# Sheet1.net
KiCad netlist of a schematic drawn in Altium Designer
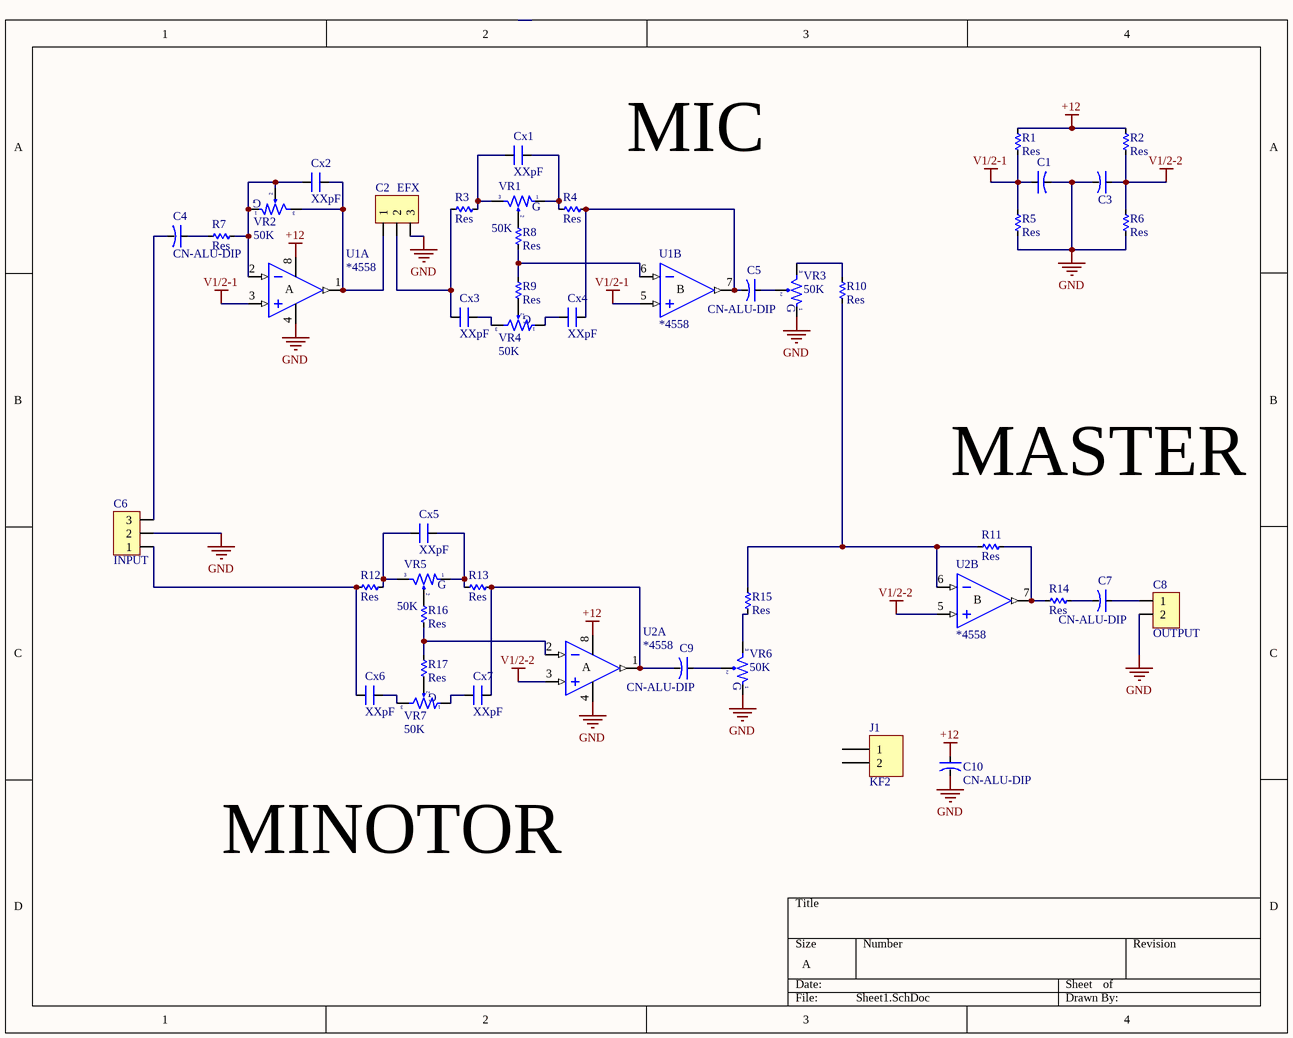
[diagram p0: Sheet1.SchDoc]

(export (version "E")
  (design (tool "Eeschema 10.0.6"))
  (components
    (comp (ref "C1")
      (value "CN-ALU-DIP")
      (footprint "CA-ALU-5")
      (description "Capacitor (Semiconductor SIM Model)")
      (fields (field (name "PUBLISHER") "Altium Limited"))
      (libsource (lib "LIBRARY") (part "CN-ALU-DIP"))
    )
    (comp (ref "C2")
      (value "EFX")
      (footprint "Header3")
      (description "Header IDC, 3 x 1 Pin Vertical 2.54mm Pitch (Non-Boxed, Male)")
      (fields
        (field (name "MANUFACTURER") "Würth Elektronik eiSos GmbH")
        (field (name "PARTNO") "613002143121")
        (field (name "CREATED BY") "Karrer Zheng")
      )
      (libsource (lib "LIBRARY") (part "Header3"))
    )
    (comp (ref "C3")
      (value "CN-ALU-DIP")
      (footprint "CA-ALU-5")
      (description "Capacitor (Semiconductor SIM Model)")
      (fields (field (name "PUBLISHER") "Altium Limited"))
      (libsource (lib "LIBRARY") (part "CN-ALU-DIP"))
    )
    (comp (ref "C4")
      (value "CN-ALU-DIP")
      (footprint "CA-ALU-5")
      (description "Capacitor (Semiconductor SIM Model)")
      (fields (field (name "PUBLISHER") "Altium Limited"))
      (libsource (lib "LIBRARY") (part "CN-ALU-DIP"))
    )
    (comp (ref "C5")
      (value "CN-ALU-DIP")
      (footprint "CA-ALU-5")
      (description "Capacitor (Semiconductor SIM Model)")
      (fields (field (name "PUBLISHER") "Altium Limited"))
      (libsource (lib "LIBRARY") (part "CN-ALU-DIP"))
    )
    (comp (ref "C6")
      (value "INPUT")
      (footprint "Header3")
      (description "Header IDC, 3 x 1 Pin Vertical 2.54mm Pitch (Non-Boxed, Male)")
      (fields
        (field (name "MANUFACTURER") "Würth Elektronik eiSos GmbH")
        (field (name "PARTNO") "613002143121")
        (field (name "CREATED BY") "Karrer Zheng")
      )
      (libsource (lib "") (part "Header3_1"))
    )
    (comp (ref "C7")
      (value "CN-ALU-DIP")
      (footprint "CA-ALU-5")
      (description "Capacitor (Semiconductor SIM Model)")
      (fields (field (name "PUBLISHER") "Altium Limited"))
      (libsource (lib "LIBRARY") (part "CN-ALU-DIP"))
    )
    (comp (ref "C8")
      (value "OUTPUT")
      (footprint "Header2")
      (description "Header IDC, 2 x 1 Pin Vertical 2.54mm Pitch (Non-Boxed, Male)")
      (fields
        (field (name "MANUFACTURER") "Würth Elektronik eiSos GmbH")
        (field (name "PARTNO") "613002143121")
        (field (name "CREATED BY") "Karrer Zheng")
      )
      (libsource (lib "LIBRARY") (part "Header2"))
    )
    (comp (ref "C9")
      (value "CN-ALU-DIP")
      (footprint "CA-ALU-5")
      (description "Capacitor (Semiconductor SIM Model)")
      (fields (field (name "PUBLISHER") "Altium Limited"))
      (libsource (lib "LIBRARY") (part "CN-ALU-DIP"))
    )
    (comp (ref "C10")
      (value "CN-ALU-DIP")
      (footprint "CA-ALU-6.3R")
      (description "Capacitor (Semiconductor SIM Model)")
      (fields (field (name "PUBLISHER") "Altium Limited"))
      (libsource (lib "") (part "CN-ALU-DIP_1"))
    )
    (comp (ref "Cx1") (value "XXpF") (footprint "CN2-O") (libsource (lib "LIBRARY") (part "CN")))
    (comp (ref "Cx2") (value "XXpF") (footprint "CN1.5") (libsource (lib "LIBRARY") (part "CN")))
    (comp (ref "Cx3") (value "XXpF") (footprint "CN2-O") (libsource (lib "LIBRARY") (part "CN")))
    (comp (ref "Cx4") (value "XXpF") (footprint "CN1.5") (libsource (lib "LIBRARY") (part "CN")))
    (comp (ref "Cx5") (value "XXpF") (footprint "CN2-O") (libsource (lib "LIBRARY") (part "CN")))
    (comp (ref "Cx6") (value "XXpF") (footprint "CN1.5") (libsource (lib "LIBRARY") (part "CN")))
    (comp (ref "Cx7") (value "XXpF") (footprint "CN1.5") (libsource (lib "LIBRARY") (part "CN")))
    (comp (ref "J1")
      (value "KF2")
      (footprint "KF2-5.08")
      (fields
        (field (name "MANUFACTURER") "Würth Elektronik eiSos GmbH")
        (field (name "PARTNO") "691103110002")
        (field (name "CREATED BY") "Karrer Zheng")
      )
      (libsource (lib "LIBRARY") (part "KF2"))
    )
    (comp (ref "R1")
      (value "Res")
      (footprint "RES-1/4W-SMALL")
      (fields
        (field (name "MANUFACTURER") "Generic Components")
        (field (name "PUBLISHER") "Altium Hobart Technology Centre")
      )
      (libsource (lib "LIBRARY") (part "Res"))
    )
    (comp (ref "R2")
      (value "Res")
      (footprint "RES-1/4W-SMALL")
      (fields
        (field (name "MANUFACTURER") "Generic Components")
        (field (name "PUBLISHER") "Altium Hobart Technology Centre")
      )
      (libsource (lib "LIBRARY") (part "Res"))
    )
    (comp (ref "R3")
      (value "Res")
      (footprint "RES-1/4W-SMALL")
      (fields
        (field (name "MANUFACTURER") "Generic Components")
        (field (name "PUBLISHER") "Altium Hobart Technology Centre")
      )
      (libsource (lib "LIBRARY") (part "Res"))
    )
    (comp (ref "R4")
      (value "Res")
      (footprint "RES-1/4W-SMALL")
      (fields
        (field (name "MANUFACTURER") "Generic Components")
        (field (name "PUBLISHER") "Altium Hobart Technology Centre")
      )
      (libsource (lib "LIBRARY") (part "Res"))
    )
    (comp (ref "R5")
      (value "Res")
      (footprint "RES-1/4W-SMALL")
      (fields
        (field (name "MANUFACTURER") "Generic Components")
        (field (name "PUBLISHER") "Altium Hobart Technology Centre")
      )
      (libsource (lib "LIBRARY") (part "Res"))
    )
    (comp (ref "R6")
      (value "Res")
      (footprint "RES-1/4W-SMALL")
      (fields
        (field (name "MANUFACTURER") "Generic Components")
        (field (name "PUBLISHER") "Altium Hobart Technology Centre")
      )
      (libsource (lib "LIBRARY") (part "Res"))
    )
    (comp (ref "R7")
      (value "Res")
      (footprint "RES-1/4W-SMALL")
      (fields
        (field (name "MANUFACTURER") "Generic Components")
        (field (name "PUBLISHER") "Altium Hobart Technology Centre")
      )
      (libsource (lib "LIBRARY") (part "Res"))
    )
    (comp (ref "R8")
      (value "Res")
      (footprint "RES-1/4W-SMALL")
      (fields
        (field (name "MANUFACTURER") "Generic Components")
        (field (name "PUBLISHER") "Altium Hobart Technology Centre")
      )
      (libsource (lib "LIBRARY") (part "Res"))
    )
    (comp (ref "R9")
      (value "Res")
      (footprint "RES-1/4W-SMALL")
      (fields
        (field (name "MANUFACTURER") "Generic Components")
        (field (name "PUBLISHER") "Altium Hobart Technology Centre")
      )
      (libsource (lib "LIBRARY") (part "Res"))
    )
    (comp (ref "R10")
      (value "Res")
      (footprint "RES-1/4W-SMALL")
      (fields
        (field (name "MANUFACTURER") "Generic Components")
        (field (name "PUBLISHER") "Altium Hobart Technology Centre")
      )
      (libsource (lib "LIBRARY") (part "Res"))
    )
    (comp (ref "R11")
      (value "Res")
      (footprint "RES-1/4W-SMALL")
      (fields
        (field (name "MANUFACTURER") "Generic Components")
        (field (name "PUBLISHER") "Altium Hobart Technology Centre")
      )
      (libsource (lib "LIBRARY") (part "Res"))
    )
    (comp (ref "R12")
      (value "Res")
      (footprint "RES-1/4W-SMALL")
      (fields
        (field (name "MANUFACTURER") "Generic Components")
        (field (name "PUBLISHER") "Altium Hobart Technology Centre")
      )
      (libsource (lib "LIBRARY") (part "Res"))
    )
    (comp (ref "R13")
      (value "Res")
      (footprint "RES-1/4W-SMALL")
      (fields
        (field (name "MANUFACTURER") "Generic Components")
        (field (name "PUBLISHER") "Altium Hobart Technology Centre")
      )
      (libsource (lib "LIBRARY") (part "Res"))
    )
    (comp (ref "R14")
      (value "Res")
      (footprint "RES-1/4W-SMALL")
      (fields
        (field (name "MANUFACTURER") "Generic Components")
        (field (name "PUBLISHER") "Altium Hobart Technology Centre")
      )
      (libsource (lib "LIBRARY") (part "Res"))
    )
    (comp (ref "R15")
      (value "Res")
      (footprint "RES-1/4W-SMALL")
      (fields
        (field (name "MANUFACTURER") "Generic Components")
        (field (name "PUBLISHER") "Altium Hobart Technology Centre")
      )
      (libsource (lib "LIBRARY") (part "Res"))
    )
    (comp (ref "R16")
      (value "Res")
      (footprint "RES-1/4W-SMALL")
      (fields
        (field (name "MANUFACTURER") "Generic Components")
        (field (name "PUBLISHER") "Altium Hobart Technology Centre")
      )
      (libsource (lib "LIBRARY") (part "Res"))
    )
    (comp (ref "R17")
      (value "Res")
      (footprint "RES-1/4W-SMALL")
      (fields
        (field (name "MANUFACTURER") "Generic Components")
        (field (name "PUBLISHER") "Altium Hobart Technology Centre")
      )
      (libsource (lib "LIBRARY") (part "Res"))
    )
    (comp (ref "U1") (value "*4558") (footprint "DIP8") (libsource (lib "LIBRARY") (part "4558")))
    (comp (ref "U2") (value "*4558") (footprint "DIP8") (libsource (lib "LIBRARY") (part "4558")))
    (comp (ref "VR1")
      (value "50K")
      (footprint "VR-S1")
      (description "Var Resistor")
      (libsource (lib "LIBRARY") (part "VR-S"))
    )
    (comp (ref "VR2")
      (value "50K")
      (footprint "VR-S2")
      (description "Var Resistor")
      (libsource (lib "LIBRARY") (part "VR-S"))
    )
    (comp (ref "VR3")
      (value "50K")
      (footprint "VR-S1")
      (description "Var Resistor")
      (libsource (lib "LIBRARY") (part "VR-S"))
    )
    (comp (ref "VR4")
      (value "50K")
      (footprint "VR-S1")
      (description "Var Resistor")
      (libsource (lib "LIBRARY") (part "VR-S"))
    )
    (comp (ref "VR5")
      (value "50K")
      (footprint "VR-S1")
      (description "Var Resistor")
      (libsource (lib "LIBRARY") (part "VR-S"))
    )
    (comp (ref "VR6")
      (value "50K")
      (footprint "VR-S1")
      (description "Var Resistor")
      (libsource (lib "LIBRARY") (part "VR-S"))
    )
    (comp (ref "VR7")
      (value "50K")
      (footprint "VR-S1")
      (description "Var Resistor")
      (libsource (lib "LIBRARY") (part "VR-S"))
    )
  )
  (nets
    (net (code "1") (name "+12") (class "Default")
      (node (ref "C10") (pin "1") (pinfunction "1_1") (pintype "passive"))
      (node (ref "R1") (pin "1") (pinfunction "1_1") (pintype "passive"))
      (node (ref "R2") (pin "1") (pinfunction "1_1") (pintype "passive"))
      (node (ref "U1") (pin "8") (pinfunction "V+_8") (pintype "power_in"))
      (node (ref "U2") (pin "8") (pinfunction "V+_8") (pintype "power_in"))
    )
    (net (code "2") (name "GND") (class "Default")
      (node (ref "C1") (pin "2") (pinfunction "2_2") (pintype "passive"))
      (node (ref "C10") (pin "2") (pinfunction "2_2") (pintype "passive"))
      (node (ref "C2") (pin "3") (pinfunction "3_3") (pintype "passive"))
      (node (ref "C3") (pin "2") (pinfunction "2_2") (pintype "passive"))
      (node (ref "C6") (pin "2") (pinfunction "2_2") (pintype "passive"))
      (node (ref "C8") (pin "2") (pinfunction "2_2") (pintype "passive"))
      (node (ref "R5") (pin "2") (pinfunction "2_2") (pintype "passive"))
      (node (ref "R6") (pin "2") (pinfunction "2_2") (pintype "passive"))
      (node (ref "U1") (pin "4") (pinfunction "V-_4") (pintype "power_in"))
      (node (ref "U2") (pin "4") (pinfunction "V-_4") (pintype "power_in"))
      (node (ref "VR3") (pin "1") (pinfunction "1_1") (pintype "passive"))
      (node (ref "VR6") (pin "1") (pinfunction "1_1") (pintype "passive"))
    )
    (net (code "3") (name "Net-(C2-Pad2)") (class "Default")
      (node (ref "C2") (pin "2") (pinfunction "2_2") (pintype "passive"))
      (node (ref "Cx3") (pin "1") (pinfunction "1_1") (pintype "passive"))
      (node (ref "R3") (pin "2") (pinfunction "2_2") (pintype "passive"))
    )
    (net (code "4") (name "Net-(C4-Pad1)") (class "Default")
      (node (ref "C4") (pin "1") (pinfunction "1_1") (pintype "passive"))
      (node (ref "R7") (pin "2") (pinfunction "2_2") (pintype "passive"))
    )
    (net (code "5") (name "Net-(C4-Pad2)") (class "Default")
      (node (ref "C4") (pin "2") (pinfunction "2_2") (pintype "passive"))
      (node (ref "C6") (pin "3") (pinfunction "3_3") (pintype "passive"))
    )
    (net (code "6") (name "Net-(C5-Pad1)") (class "Default")
      (node (ref "C5") (pin "1") (pinfunction "1_1") (pintype "passive"))
      (node (ref "VR3") (pin "2") (pinfunction "2_2") (pintype "passive"))
    )
    (net (code "7") (name "Net-(C6-Pad1)") (class "Default")
      (node (ref "C6") (pin "1") (pinfunction "1_1") (pintype "passive"))
      (node (ref "Cx6") (pin "1") (pinfunction "1_1") (pintype "passive"))
      (node (ref "R12") (pin "2") (pinfunction "2_2") (pintype "passive"))
    )
    (net (code "8") (name "Net-(C7-Pad1)") (class "Default")
      (node (ref "C7") (pin "1") (pinfunction "1_1") (pintype "passive"))
      (node (ref "C8") (pin "1") (pinfunction "1_1") (pintype "passive"))
    )
    (net (code "9") (name "Net-(C7-Pad2)") (class "Default")
      (node (ref "C7") (pin "2") (pinfunction "2_2") (pintype "passive"))
      (node (ref "R14") (pin "1") (pinfunction "1_1") (pintype "passive"))
    )
    (net (code "10") (name "Net-(C9-Pad1)") (class "Default")
      (node (ref "C9") (pin "1") (pinfunction "1_1") (pintype "passive"))
      (node (ref "VR6") (pin "2") (pinfunction "2_2") (pintype "passive"))
    )
    (net (code "11") (name "Net-(Cx1-Pad1)") (class "Default")
      (node (ref "Cx1") (pin "1") (pinfunction "1_1") (pintype "passive"))
      (node (ref "R3") (pin "1") (pinfunction "1_1") (pintype "passive"))
      (node (ref "VR1") (pin "3") (pinfunction "3_3") (pintype "passive"))
    )
    (net (code "12") (name "Net-(Cx1-Pad2)") (class "Default")
      (node (ref "Cx1") (pin "2") (pinfunction "2_2") (pintype "passive"))
      (node (ref "R4") (pin "2") (pinfunction "2_2") (pintype "passive"))
      (node (ref "VR1") (pin "1") (pinfunction "1_1") (pintype "passive"))
    )
    (net (code "13") (name "Net-(Cx3-Pad2)") (class "Default")
      (node (ref "Cx3") (pin "2") (pinfunction "2_2") (pintype "passive"))
      (node (ref "VR4") (pin "3") (pinfunction "3_3") (pintype "passive"))
    )
    (net (code "14") (name "Net-(Cx4-Pad1)") (class "Default")
      (node (ref "Cx4") (pin "1") (pinfunction "1_1") (pintype "passive"))
      (node (ref "VR4") (pin "1") (pinfunction "1_1") (pintype "passive"))
    )
    (net (code "15") (name "Net-(Cx5-Pad1)") (class "Default")
      (node (ref "Cx5") (pin "1") (pinfunction "1_1") (pintype "passive"))
      (node (ref "R12") (pin "1") (pinfunction "1_1") (pintype "passive"))
      (node (ref "VR5") (pin "3") (pinfunction "3_3") (pintype "passive"))
    )
    (net (code "16") (name "Net-(Cx5-Pad2)") (class "Default")
      (node (ref "Cx5") (pin "2") (pinfunction "2_2") (pintype "passive"))
      (node (ref "R13") (pin "2") (pinfunction "2_2") (pintype "passive"))
      (node (ref "VR5") (pin "1") (pinfunction "1_1") (pintype "passive"))
    )
    (net (code "17") (name "Net-(Cx6-Pad2)") (class "Default")
      (node (ref "Cx6") (pin "2") (pinfunction "2_2") (pintype "passive"))
      (node (ref "VR7") (pin "3") (pinfunction "3_3") (pintype "passive"))
    )
    (net (code "18") (name "Net-(Cx7-Pad1)") (class "Default")
      (node (ref "Cx7") (pin "1") (pinfunction "1_1") (pintype "passive"))
      (node (ref "VR7") (pin "1") (pinfunction "1_1") (pintype "passive"))
    )
    (net (code "19") (name "Net-(R8-Pad1)") (class "Default")
      (node (ref "R8") (pin "1") (pinfunction "1_1") (pintype "passive"))
      (node (ref "VR1") (pin "2") (pinfunction "2_2") (pintype "passive"))
    )
    (net (code "20") (name "Net-(R9-Pad2)") (class "Default")
      (node (ref "R9") (pin "2") (pinfunction "2_2") (pintype "passive"))
      (node (ref "VR4") (pin "2") (pinfunction "2_2") (pintype "passive"))
    )
    (net (code "21") (name "Net-(R10-Pad1)") (class "Default")
      (node (ref "R10") (pin "1") (pinfunction "1_1") (pintype "passive"))
      (node (ref "VR3") (pin "3") (pinfunction "3_3") (pintype "passive"))
    )
    (net (code "22") (name "Net-(R15-Pad2)") (class "Default")
      (node (ref "R15") (pin "2") (pinfunction "2_2") (pintype "passive"))
      (node (ref "VR6") (pin "3") (pinfunction "3_3") (pintype "passive"))
    )
    (net (code "23") (name "Net-(R16-Pad1)") (class "Default")
      (node (ref "R16") (pin "1") (pinfunction "1_1") (pintype "passive"))
      (node (ref "VR5") (pin "2") (pinfunction "2_2") (pintype "passive"))
    )
    (net (code "24") (name "Net-(R17-Pad2)") (class "Default")
      (node (ref "R17") (pin "2") (pinfunction "2_2") (pintype "passive"))
      (node (ref "VR7") (pin "2") (pinfunction "2_2") (pintype "passive"))
    )
    (net (code "25") (name "Net-(U1A-IN-)") (class "Default")
      (node (ref "Cx2") (pin "1") (pinfunction "1_1") (pintype "passive"))
      (node (ref "R7") (pin "1") (pinfunction "1_1") (pintype "passive"))
      (node (ref "U1") (pin "2") (pinfunction "IN-_2") (pintype "input"))
      (node (ref "VR2") (pin "1") (pinfunction "1_1") (pintype "passive"))
      (node (ref "VR2") (pin "2") (pinfunction "2_2") (pintype "passive"))
    )
    (net (code "26") (name "Net-(U1A-OUT)") (class "Default")
      (node (ref "C2") (pin "1") (pinfunction "1_1") (pintype "passive"))
      (node (ref "Cx2") (pin "2") (pinfunction "2_2") (pintype "passive"))
      (node (ref "U1") (pin "1") (pinfunction "OUT_1") (pintype "output"))
      (node (ref "VR2") (pin "3") (pinfunction "3_3") (pintype "passive"))
    )
    (net (code "27") (name "Net-(U1B-IN-)") (class "Default")
      (node (ref "R8") (pin "2") (pinfunction "2_2") (pintype "passive"))
      (node (ref "R9") (pin "1") (pinfunction "1_1") (pintype "passive"))
      (node (ref "U1") (pin "6") (pinfunction "IN-_6") (pintype "input"))
    )
    (net (code "28") (name "Net-(U1B-OUT)") (class "Default")
      (node (ref "C5") (pin "2") (pinfunction "2_2") (pintype "passive"))
      (node (ref "Cx4") (pin "2") (pinfunction "2_2") (pintype "passive"))
      (node (ref "R4") (pin "1") (pinfunction "1_1") (pintype "passive"))
      (node (ref "U1") (pin "7") (pinfunction "OUT_7") (pintype "output"))
    )
    (net (code "29") (name "Net-(U2A-IN-)") (class "Default")
      (node (ref "R16") (pin "2") (pinfunction "2_2") (pintype "passive"))
      (node (ref "R17") (pin "1") (pinfunction "1_1") (pintype "passive"))
      (node (ref "U2") (pin "2") (pinfunction "IN-_2") (pintype "input"))
    )
    (net (code "30") (name "Net-(U2A-OUT)") (class "Default")
      (node (ref "C9") (pin "2") (pinfunction "2_2") (pintype "passive"))
      (node (ref "Cx7") (pin "2") (pinfunction "2_2") (pintype "passive"))
      (node (ref "R13") (pin "1") (pinfunction "1_1") (pintype "passive"))
      (node (ref "U2") (pin "1") (pinfunction "OUT_1") (pintype "output"))
    )
    (net (code "31") (name "Net-(U2B-IN-)") (class "Default")
      (node (ref "R10") (pin "2") (pinfunction "2_2") (pintype "passive"))
      (node (ref "R11") (pin "2") (pinfunction "2_2") (pintype "passive"))
      (node (ref "R15") (pin "1") (pinfunction "1_1") (pintype "passive"))
      (node (ref "U2") (pin "6") (pinfunction "IN-_6") (pintype "input"))
    )
    (net (code "32") (name "Net-(U2B-OUT)") (class "Default")
      (node (ref "R11") (pin "1") (pinfunction "1_1") (pintype "passive"))
      (node (ref "R14") (pin "2") (pinfunction "2_2") (pintype "passive"))
      (node (ref "U2") (pin "7") (pinfunction "OUT_7") (pintype "output"))
    )
    (net (code "33") (name "V1{slash}2-1") (class "Default")
      (node (ref "C1") (pin "1") (pinfunction "1_1") (pintype "passive"))
      (node (ref "R1") (pin "2") (pinfunction "2_2") (pintype "passive"))
      (node (ref "R5") (pin "1") (pinfunction "1_1") (pintype "passive"))
      (node (ref "U1") (pin "3") (pinfunction "IN+_3") (pintype "input"))
      (node (ref "U1") (pin "5") (pinfunction "IN+_5") (pintype "input"))
    )
    (net (code "34") (name "V1{slash}2-2") (class "Default")
      (node (ref "C3") (pin "1") (pinfunction "1_1") (pintype "passive"))
      (node (ref "R2") (pin "2") (pinfunction "2_2") (pintype "passive"))
      (node (ref "R6") (pin "1") (pinfunction "1_1") (pintype "passive"))
      (node (ref "U2") (pin "3") (pinfunction "IN+_3") (pintype "input"))
      (node (ref "U2") (pin "5") (pinfunction "IN+_5") (pintype "input"))
    )
    (net (code "35") (name "unconnected-(J1-Pad1)") (class "Default")
      (node (ref "J1") (pin "1") (pinfunction "1_1") (pintype "passive"))
    )
    (net (code "36") (name "unconnected-(J1-Pad2)") (class "Default")
      (node (ref "J1") (pin "2") (pinfunction "2_2") (pintype "passive"))
    )
  )
)
